# input_protection.net
KiCad netlist of a schematic drawn in Altium Designer
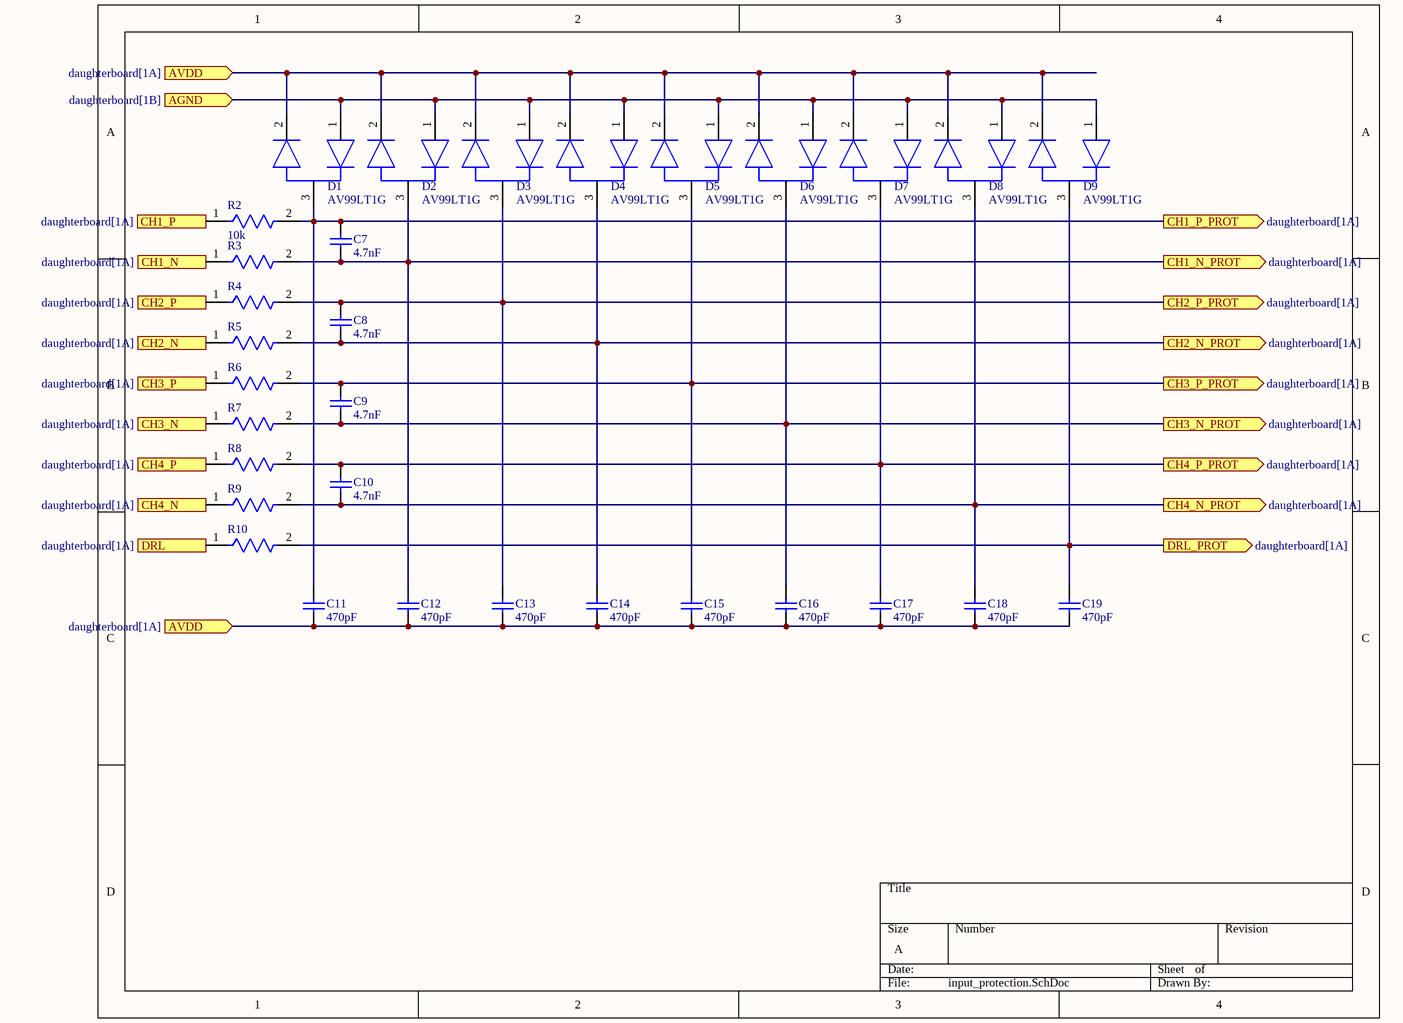
[diagram p0: input_protection.SchDoc]

(export (version "E")
  (design (tool "Eeschema 10.0.6"))
  (components
    (comp (ref "C7")
      (value "4.7nF")
      (footprint "CAPC2013X145X48ML20T23")
      (fields (field (name "PART NUMBER") "VJ0805Y472KXBMC") (field (name "MANUFACTURER") "Vitramon"))
      (libsource (lib "Altium Content Vault") (part "CAP"))
    )
    (comp (ref "C8")
      (value "4.7nF")
      (footprint "CAPC2013X145X48ML20T23")
      (fields (field (name "PART NUMBER") "VJ0805Y472KXBMC") (field (name "MANUFACTURER") "Vitramon"))
      (libsource (lib "Altium Content Vault") (part "CAP"))
    )
    (comp (ref "C9")
      (value "4.7nF")
      (footprint "CAPC2013X145X48ML20T23")
      (fields (field (name "PART NUMBER") "VJ0805Y472KXBMC") (field (name "MANUFACTURER") "Vitramon"))
      (libsource (lib "Altium Content Vault") (part "CAP"))
    )
    (comp (ref "C10")
      (value "4.7nF")
      (footprint "CAPC2013X145X48ML20T23")
      (fields (field (name "PART NUMBER") "VJ0805Y472KXBMC") (field (name "MANUFACTURER") "Vitramon"))
      (libsource (lib "Altium Content Vault") (part "CAP"))
    )
    (comp (ref "C11")
      (value "470pF")
      (footprint "CAPC2013X145X48NL20T23")
      (fields (field (name "PART NUMBER") "VJ0805A471JXBMC") (field (name "MANUFACTURER") "Vitramon"))
      (libsource (lib "Altium Content Vault") (part "CAP"))
    )
    (comp (ref "C12")
      (value "470pF")
      (footprint "CAPC2013X145X48NL20T23")
      (fields (field (name "PART NUMBER") "VJ0805A471JXBMC") (field (name "MANUFACTURER") "Vitramon"))
      (libsource (lib "Altium Content Vault") (part "CAP"))
    )
    (comp (ref "C13")
      (value "470pF")
      (footprint "CAPC2013X145X48NL20T23")
      (fields (field (name "PART NUMBER") "VJ0805A471JXBMC") (field (name "MANUFACTURER") "Vitramon"))
      (libsource (lib "Altium Content Vault") (part "CAP"))
    )
    (comp (ref "C14")
      (value "470pF")
      (footprint "CAPC2013X145X48NL20T23")
      (fields (field (name "PART NUMBER") "VJ0805A471JXBMC") (field (name "MANUFACTURER") "Vitramon"))
      (libsource (lib "Altium Content Vault") (part "CAP"))
    )
    (comp (ref "C15")
      (value "470pF")
      (footprint "CAPC2013X145X48NL20T23")
      (fields (field (name "PART NUMBER") "VJ0805A471JXBMC") (field (name "MANUFACTURER") "Vitramon"))
      (libsource (lib "Altium Content Vault") (part "CAP"))
    )
    (comp (ref "C16")
      (value "470pF")
      (footprint "CAPC2013X145X48NL20T23")
      (fields (field (name "PART NUMBER") "VJ0805A471JXBMC") (field (name "MANUFACTURER") "Vitramon"))
      (libsource (lib "Altium Content Vault") (part "CAP"))
    )
    (comp (ref "C17")
      (value "470pF")
      (footprint "CAPC2013X145X48NL20T23")
      (fields (field (name "PART NUMBER") "VJ0805A471JXBMC") (field (name "MANUFACTURER") "Vitramon"))
      (libsource (lib "Altium Content Vault") (part "CAP"))
    )
    (comp (ref "C18")
      (value "470pF")
      (footprint "CAPC2013X145X48NL20T23")
      (fields (field (name "PART NUMBER") "VJ0805A471JXBMC") (field (name "MANUFACTURER") "Vitramon"))
      (libsource (lib "Altium Content Vault") (part "CAP"))
    )
    (comp (ref "C19")
      (value "470pF")
      (footprint "CAPC2013X145X48NL20T23")
      (fields (field (name "PART NUMBER") "VJ0805A471JXBMC") (field (name "MANUFACTURER") "Vitramon"))
      (libsource (lib "Altium Content Vault") (part "CAP"))
    )
    (comp (ref "D1")
      (value "AV99LT1G")
      (footprint "FP-318-08-IPC_B")
      (description "DIODE ARRAY 100V 215MA SOT23-3")
      (libsource (lib "Altium Content Vault") (part "7b418a28e9680f52904df7990ac9ce6"))
    )
    (comp (ref "D2")
      (value "AV99LT1G")
      (footprint "FP-318-08-IPC_B")
      (description "DIODE ARRAY 100V 215MA SOT23-3")
      (libsource (lib "Altium Content Vault") (part "7b418a28e9680f52904df7990ac9ce6"))
    )
    (comp (ref "D3")
      (value "AV99LT1G")
      (footprint "FP-318-08-IPC_B")
      (description "DIODE ARRAY 100V 215MA SOT23-3")
      (libsource (lib "Altium Content Vault") (part "7b418a28e9680f52904df7990ac9ce6"))
    )
    (comp (ref "D4")
      (value "AV99LT1G")
      (footprint "FP-318-08-IPC_B")
      (description "DIODE ARRAY 100V 215MA SOT23-3")
      (libsource (lib "Altium Content Vault") (part "7b418a28e9680f52904df7990ac9ce6"))
    )
    (comp (ref "D5")
      (value "AV99LT1G")
      (footprint "FP-318-08-IPC_B")
      (description "DIODE ARRAY 100V 215MA SOT23-3")
      (libsource (lib "Altium Content Vault") (part "7b418a28e9680f52904df7990ac9ce6"))
    )
    (comp (ref "D6")
      (value "AV99LT1G")
      (footprint "FP-318-08-IPC_B")
      (description "DIODE ARRAY 100V 215MA SOT23-3")
      (libsource (lib "Altium Content Vault") (part "7b418a28e9680f52904df7990ac9ce6"))
    )
    (comp (ref "D7")
      (value "AV99LT1G")
      (footprint "FP-318-08-IPC_B")
      (description "DIODE ARRAY 100V 215MA SOT23-3")
      (libsource (lib "Altium Content Vault") (part "7b418a28e9680f52904df7990ac9ce6"))
    )
    (comp (ref "D8")
      (value "AV99LT1G")
      (footprint "FP-318-08-IPC_B")
      (description "DIODE ARRAY 100V 215MA SOT23-3")
      (libsource (lib "Altium Content Vault") (part "7b418a28e9680f52904df7990ac9ce6"))
    )
    (comp (ref "D9")
      (value "AV99LT1G")
      (footprint "FP-318-08-IPC_B")
      (description "DIODE ARRAY 100V 215MA SOT23-3")
      (libsource (lib "Altium Content Vault") (part "7b418a28e9680f52904df7990ac9ce6"))
    )
    (comp (ref "R2")
      (value "10k")
      (footprint "FP-RN73R2B-MFG")
      (description "1kΩ ±1% 0.25W, 1/4W Chip Resistor 1206 (3216 Metric) Moisture Resistant Thin Film")
      (libsource (lib "Altium Content Vault") (part "1029c3af85768c4190bb7ad29bc67b5"))
    )
    (comp (ref "R3")
      (value "10k - RN73R2BTTD1001F25")
      (footprint "FP-RN73R2B-MFG")
      (description "1kΩ ±1% 0.25W, 1/4W Chip Resistor 1206 (3216 Metric) Moisture Resistant Thin Film")
      (libsource (lib "Altium Content Vault") (part "1029c3af85768c4190bb7ad29bc67b5"))
    )
    (comp (ref "R4")
      (value "10k - RN73R2BTTD1001F25")
      (footprint "FP-RN73R2B-MFG")
      (description "1kΩ ±1% 0.25W, 1/4W Chip Resistor 1206 (3216 Metric) Moisture Resistant Thin Film")
      (libsource (lib "Altium Content Vault") (part "1029c3af85768c4190bb7ad29bc67b5"))
    )
    (comp (ref "R5")
      (value "10k - RN73R2BTTD1001F25")
      (footprint "FP-RN73R2B-MFG")
      (description "1kΩ ±1% 0.25W, 1/4W Chip Resistor 1206 (3216 Metric) Moisture Resistant Thin Film")
      (libsource (lib "Altium Content Vault") (part "1029c3af85768c4190bb7ad29bc67b5"))
    )
    (comp (ref "R6")
      (value "10k - RN73R2BTTD1001F25")
      (footprint "FP-RN73R2B-MFG")
      (description "1kΩ ±1% 0.25W, 1/4W Chip Resistor 1206 (3216 Metric) Moisture Resistant Thin Film")
      (libsource (lib "Altium Content Vault") (part "1029c3af85768c4190bb7ad29bc67b5"))
    )
    (comp (ref "R7")
      (value "10k - RN73R2BTTD1001F25")
      (footprint "FP-RN73R2B-MFG")
      (description "1kΩ ±1% 0.25W, 1/4W Chip Resistor 1206 (3216 Metric) Moisture Resistant Thin Film")
      (libsource (lib "Altium Content Vault") (part "1029c3af85768c4190bb7ad29bc67b5"))
    )
    (comp (ref "R8")
      (value "10k - RN73R2BTTD1001F25")
      (footprint "FP-RN73R2B-MFG")
      (description "1kΩ ±1% 0.25W, 1/4W Chip Resistor 1206 (3216 Metric) Moisture Resistant Thin Film")
      (libsource (lib "Altium Content Vault") (part "1029c3af85768c4190bb7ad29bc67b5"))
    )
    (comp (ref "R9")
      (value "10k - RN73R2BTTD1001F25")
      (footprint "FP-RN73R2B-MFG")
      (description "1kΩ ±1% 0.25W, 1/4W Chip Resistor 1206 (3216 Metric) Moisture Resistant Thin Film")
      (libsource (lib "Altium Content Vault") (part "1029c3af85768c4190bb7ad29bc67b5"))
    )
    (comp (ref "R10")
      (value "10k - RN73R2BTTD1001F25")
      (footprint "FP-RN73R2B-MFG")
      (description "1kΩ ±1% 0.25W, 1/4W Chip Resistor 1206 (3216 Metric) Moisture Resistant Thin Film")
      (libsource (lib "Altium Content Vault") (part "1029c3af85768c4190bb7ad29bc67b5"))
    )
  )
  (nets
    (net (code "1") (name "/AGND") (class "Default")
      (node (ref "D1") (pin "1") (pinfunction "A_1") (pintype "passive"))
      (node (ref "D2") (pin "1") (pinfunction "A_1") (pintype "passive"))
      (node (ref "D3") (pin "1") (pinfunction "A_1") (pintype "passive"))
      (node (ref "D4") (pin "1") (pinfunction "A_1") (pintype "passive"))
      (node (ref "D5") (pin "1") (pinfunction "A_1") (pintype "passive"))
      (node (ref "D6") (pin "1") (pinfunction "A_1") (pintype "passive"))
      (node (ref "D7") (pin "1") (pinfunction "A_1") (pintype "passive"))
      (node (ref "D8") (pin "1") (pinfunction "A_1") (pintype "passive"))
      (node (ref "D9") (pin "1") (pinfunction "A_1") (pintype "passive"))
    )
    (net (code "2") (name "/AVDD") (class "Default")
      (node (ref "C11") (pin "1") (pinfunction "1_1") (pintype "passive"))
      (node (ref "C12") (pin "1") (pinfunction "1_1") (pintype "passive"))
      (node (ref "C13") (pin "1") (pinfunction "1_1") (pintype "passive"))
      (node (ref "C14") (pin "1") (pinfunction "1_1") (pintype "passive"))
      (node (ref "C15") (pin "1") (pinfunction "1_1") (pintype "passive"))
      (node (ref "C16") (pin "1") (pinfunction "1_1") (pintype "passive"))
      (node (ref "C17") (pin "1") (pinfunction "1_1") (pintype "passive"))
      (node (ref "C18") (pin "1") (pinfunction "1_1") (pintype "passive"))
      (node (ref "C19") (pin "1") (pinfunction "1_1") (pintype "passive"))
      (node (ref "D1") (pin "2") (pinfunction "C_2") (pintype "passive"))
      (node (ref "D2") (pin "2") (pinfunction "C_2") (pintype "passive"))
      (node (ref "D3") (pin "2") (pinfunction "C_2") (pintype "passive"))
      (node (ref "D4") (pin "2") (pinfunction "C_2") (pintype "passive"))
      (node (ref "D5") (pin "2") (pinfunction "C_2") (pintype "passive"))
      (node (ref "D6") (pin "2") (pinfunction "C_2") (pintype "passive"))
      (node (ref "D7") (pin "2") (pinfunction "C_2") (pintype "passive"))
      (node (ref "D8") (pin "2") (pinfunction "C_2") (pintype "passive"))
      (node (ref "D9") (pin "2") (pinfunction "C_2") (pintype "passive"))
    )
    (net (code "3") (name "/CH1_N") (class "Default")
      (node (ref "R3") (pin "1") (pinfunction "1_1") (pintype "passive"))
    )
    (net (code "4") (name "/CH1_N_PROT") (class "Default")
      (node (ref "C12") (pin "2") (pinfunction "2_2") (pintype "passive"))
      (node (ref "C7") (pin "1") (pinfunction "1_1") (pintype "passive"))
      (node (ref "D2") (pin "3") (pinfunction "CATHODE/ANODE_3") (pintype "passive"))
      (node (ref "R3") (pin "2") (pinfunction "2_2") (pintype "passive"))
    )
    (net (code "5") (name "/CH1_P") (class "Default")
      (node (ref "R2") (pin "1") (pinfunction "1_1") (pintype "passive"))
    )
    (net (code "6") (name "/CH1_P_PROT") (class "Default")
      (node (ref "C11") (pin "2") (pinfunction "2_2") (pintype "passive"))
      (node (ref "C7") (pin "2") (pinfunction "2_2") (pintype "passive"))
      (node (ref "D1") (pin "3") (pinfunction "CATHODE/ANODE_3") (pintype "passive"))
      (node (ref "R2") (pin "2") (pinfunction "2_2") (pintype "passive"))
    )
    (net (code "7") (name "/CH2_N") (class "Default")
      (node (ref "R5") (pin "1") (pinfunction "1_1") (pintype "passive"))
    )
    (net (code "8") (name "/CH2_N_PROT") (class "Default")
      (node (ref "C14") (pin "2") (pinfunction "2_2") (pintype "passive"))
      (node (ref "C8") (pin "1") (pinfunction "1_1") (pintype "passive"))
      (node (ref "D4") (pin "3") (pinfunction "CATHODE/ANODE_3") (pintype "passive"))
      (node (ref "R5") (pin "2") (pinfunction "2_2") (pintype "passive"))
    )
    (net (code "9") (name "/CH2_P") (class "Default")
      (node (ref "R4") (pin "1") (pinfunction "1_1") (pintype "passive"))
    )
    (net (code "10") (name "/CH2_P_PROT") (class "Default")
      (node (ref "C13") (pin "2") (pinfunction "2_2") (pintype "passive"))
      (node (ref "C8") (pin "2") (pinfunction "2_2") (pintype "passive"))
      (node (ref "D3") (pin "3") (pinfunction "CATHODE/ANODE_3") (pintype "passive"))
      (node (ref "R4") (pin "2") (pinfunction "2_2") (pintype "passive"))
    )
    (net (code "11") (name "/CH3_N") (class "Default")
      (node (ref "R7") (pin "1") (pinfunction "1_1") (pintype "passive"))
    )
    (net (code "12") (name "/CH3_N_PROT") (class "Default")
      (node (ref "C16") (pin "2") (pinfunction "2_2") (pintype "passive"))
      (node (ref "C9") (pin "1") (pinfunction "1_1") (pintype "passive"))
      (node (ref "D6") (pin "3") (pinfunction "CATHODE/ANODE_3") (pintype "passive"))
      (node (ref "R7") (pin "2") (pinfunction "2_2") (pintype "passive"))
    )
    (net (code "13") (name "/CH3_P") (class "Default")
      (node (ref "R6") (pin "1") (pinfunction "1_1") (pintype "passive"))
    )
    (net (code "14") (name "/CH3_P_PROT") (class "Default")
      (node (ref "C15") (pin "2") (pinfunction "2_2") (pintype "passive"))
      (node (ref "C9") (pin "2") (pinfunction "2_2") (pintype "passive"))
      (node (ref "D5") (pin "3") (pinfunction "CATHODE/ANODE_3") (pintype "passive"))
      (node (ref "R6") (pin "2") (pinfunction "2_2") (pintype "passive"))
    )
    (net (code "15") (name "/CH4_N") (class "Default")
      (node (ref "R9") (pin "1") (pinfunction "1_1") (pintype "passive"))
    )
    (net (code "16") (name "/CH4_N_PROT") (class "Default")
      (node (ref "C10") (pin "1") (pinfunction "1_1") (pintype "passive"))
      (node (ref "C18") (pin "2") (pinfunction "2_2") (pintype "passive"))
      (node (ref "D8") (pin "3") (pinfunction "CATHODE/ANODE_3") (pintype "passive"))
      (node (ref "R9") (pin "2") (pinfunction "2_2") (pintype "passive"))
    )
    (net (code "17") (name "/CH4_P") (class "Default")
      (node (ref "R8") (pin "1") (pinfunction "1_1") (pintype "passive"))
    )
    (net (code "18") (name "/CH4_P_PROT") (class "Default")
      (node (ref "C10") (pin "2") (pinfunction "2_2") (pintype "passive"))
      (node (ref "C17") (pin "2") (pinfunction "2_2") (pintype "passive"))
      (node (ref "D7") (pin "3") (pinfunction "CATHODE/ANODE_3") (pintype "passive"))
      (node (ref "R8") (pin "2") (pinfunction "2_2") (pintype "passive"))
    )
    (net (code "19") (name "/DRL") (class "Default")
      (node (ref "R10") (pin "1") (pinfunction "1_1") (pintype "passive"))
    )
    (net (code "20") (name "/DRL_PROT") (class "Default")
      (node (ref "C19") (pin "2") (pinfunction "2_2") (pintype "passive"))
      (node (ref "D9") (pin "3") (pinfunction "CATHODE/ANODE_3") (pintype "passive"))
      (node (ref "R10") (pin "2") (pinfunction "2_2") (pintype "passive"))
    )
  )
)
